# PA93_Periphery.net
KiCad netlist of a schematic drawn in Altium Designer
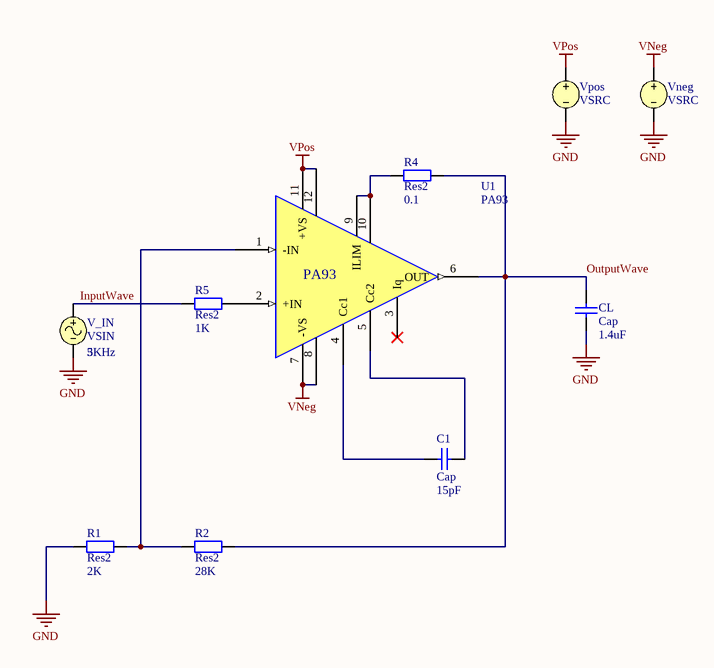
[diagram p0: PA93_Periphery.SchDoc]

(export (version "E")
  (design (tool "Eeschema 10.0.6"))
  (components
    (comp (ref "C1")
      (value "Cap")
      (footprint "RAD-0.3")
      (description "Capacitor")
      (fields (field (name "ALTIUM_VALUE") "15pF") (field (name "PUBLISHER") "Altium Limited"))
      (libsource (lib "Miscellaneous Devices") (part "Cap"))
    )
    (comp (ref "CL")
      (value "Cap")
      (footprint "RAD-0.3")
      (description "Capacitor")
      (fields (field (name "ALTIUM_VALUE") "1.4uF") (field (name "PUBLISHER") "Altium Limited"))
      (libsource (lib "Miscellaneous Devices") (part "Cap"))
    )
    (comp (ref "R1")
      (value "Res2")
      (footprint "AXIAL-0.4")
      (description "Resistor")
      (fields (field (name "ALTIUM_VALUE") "2K") (field (name "PUBLISHER") "Altium Limited"))
      (libsource (lib "Miscellaneous Devices") (part "Res2"))
    )
    (comp (ref "R2")
      (value "Res2")
      (footprint "AXIAL-0.4")
      (description "Resistor")
      (fields (field (name "ALTIUM_VALUE") "28K") (field (name "PUBLISHER") "Altium Limited"))
      (libsource (lib "Miscellaneous Devices") (part "Res2"))
    )
    (comp (ref "R4")
      (value "Res2")
      (footprint "AXIAL-0.4")
      (description "Resistor")
      (fields (field (name "ALTIUM_VALUE") "0.1") (field (name "PUBLISHER") "Altium Limited"))
      (libsource (lib "Miscellaneous Devices") (part "Res2"))
    )
    (comp (ref "R5")
      (value "Res2")
      (footprint "AXIAL-0.4")
      (description "Resistor")
      (fields (field (name "ALTIUM_VALUE") "1K") (field (name "PUBLISHER") "Altium Limited"))
      (libsource (lib "Miscellaneous Devices") (part "Res2"))
    )
    (comp (ref "U1") (value "PA93") (libsource (lib "PA93") (part "PA93")))
    (comp (ref "Vneg")
      (value "VSRC")
      (description "Voltage Source")
      (fields (field (name "PUBLISHER") "Altium Limited"))
      (libsource (lib "Simulation Sources") (part "VSRC"))
    )
    (comp (ref "Vpos")
      (value "VSRC")
      (description "Voltage Source")
      (fields (field (name "PUBLISHER") "Altium Limited"))
      (libsource (lib "Simulation Sources") (part "VSRC"))
    )
    (comp (ref "V_IN")
      (value "VSIN")
      (description "Sinusoidal Voltage Source")
      (fields
        (field (name "AC MAGNITUDE") "5")
        (field (name "OFFSET") "5")
        (field (name "AMPLITUDE") "5")
        (field (name "FREQUENCY") "3KHz")
        (field (name "PUBLISHER") "Altium Limited")
      )
      (libsource (lib "Simulation Sources") (part "VSIN"))
    )
  )
  (nets
    (net (code "1") (name "/InputWave") (class "Default")
      (node (ref "R5") (pin "1") (pinfunction "1_1") (pintype "passive"))
      (node (ref "V_IN") (pin "1") (pinfunction "1_1") (pintype "passive"))
    )
    (net (code "2") (name "/OutputWave") (class "Default")
      (node (ref "CL") (pin "2") (pinfunction "2_2") (pintype "passive"))
      (node (ref "R2") (pin "2") (pinfunction "2_2") (pintype "passive"))
      (node (ref "R4") (pin "2") (pinfunction "2_2") (pintype "passive"))
      (node (ref "U1") (pin "6") (pinfunction "OUT_6") (pintype "output"))
    )
    (net (code "3") (name "GND") (class "Default")
      (node (ref "CL") (pin "1") (pinfunction "1_1") (pintype "passive"))
      (node (ref "R1") (pin "1") (pinfunction "1_1") (pintype "passive"))
      (node (ref "V_IN") (pin "2") (pinfunction "2_2") (pintype "passive"))
      (node (ref "Vneg") (pin "2") (pinfunction "2_2") (pintype "passive"))
      (node (ref "Vpos") (pin "2") (pinfunction "2_2") (pintype "passive"))
    )
    (net (code "4") (name "Net-(R4-Pad1)") (class "Default")
      (node (ref "R4") (pin "1") (pinfunction "1_1") (pintype "passive"))
      (node (ref "U1") (pin "10") (pinfunction "ILIM_10") (pintype "passive"))
      (node (ref "U1") (pin "9") (pinfunction "ILIM_9") (pintype "passive"))
    )
    (net (code "5") (name "Net-(U1-+IN)") (class "Default")
      (node (ref "R5") (pin "2") (pinfunction "2_2") (pintype "passive"))
      (node (ref "U1") (pin "2") (pinfunction "+IN_2") (pintype "input"))
    )
    (net (code "6") (name "Net-(U1--IN)") (class "Default")
      (node (ref "R1") (pin "2") (pinfunction "2_2") (pintype "passive"))
      (node (ref "R2") (pin "1") (pinfunction "1_1") (pintype "passive"))
      (node (ref "U1") (pin "1") (pinfunction "-IN_1") (pintype "input"))
    )
    (net (code "7") (name "Net-(U1-Cc1)") (class "Default")
      (node (ref "C1") (pin "1") (pinfunction "1_1") (pintype "passive"))
      (node (ref "U1") (pin "4") (pinfunction "Cc1_4") (pintype "passive"))
    )
    (net (code "8") (name "Net-(U1-Cc2)") (class "Default")
      (node (ref "C1") (pin "2") (pinfunction "2_2") (pintype "passive"))
      (node (ref "U1") (pin "5") (pinfunction "Cc2_5") (pintype "passive"))
    )
    (net (code "9") (name "VNeg") (class "Default")
      (node (ref "U1") (pin "7") (pinfunction "-VS_7") (pintype "passive"))
      (node (ref "U1") (pin "8") (pinfunction "-VS_8") (pintype "passive"))
      (node (ref "Vneg") (pin "1") (pinfunction "1_1") (pintype "passive"))
    )
    (net (code "10") (name "VPos") (class "Default")
      (node (ref "U1") (pin "11") (pinfunction "+VS_11") (pintype "passive"))
      (node (ref "U1") (pin "12") (pinfunction "+VS_12") (pintype "passive"))
      (node (ref "Vpos") (pin "1") (pinfunction "1_1") (pintype "passive"))
    )
    (net (code "11") (name "unconnected-(U1-Iq-Pad3)") (class "Default")
      (node (ref "U1") (pin "3") (pinfunction "Iq_3") (pintype "passive+no_connect"))
    )
  )
)
